# DoorSensor-v1_0.net
KiCad netlist of a schematic drawn in EAGLE
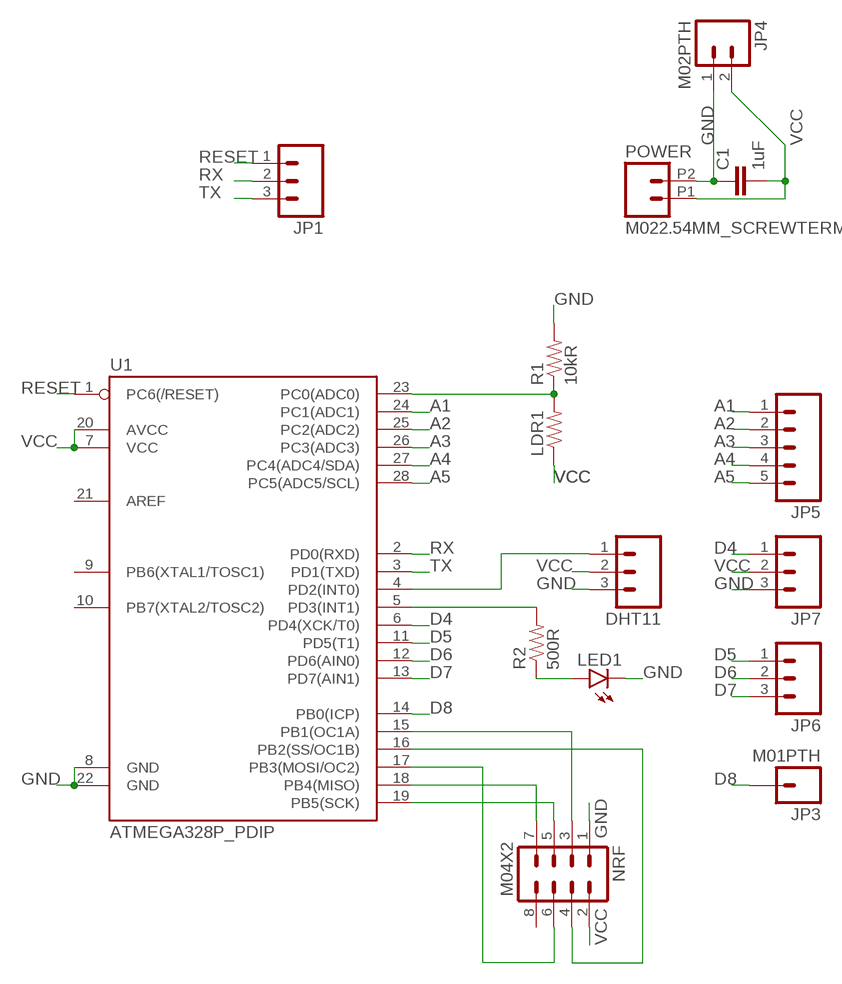
[diagram p0: schematic, sheet 1]

(export (version "E")
  (design (tool "Eeschema 10.0.6"))
  (components
    (comp (ref "C1")
      (value "1uF")
      (footprint "eagle-import:CAP-PTH-SMALL")
      (libsource (lib "eagle-import") (part "CAPPTH"))
    )
    (comp (ref "DHT11")
      (value "M03PTH")
      (footprint "eagle-import:1X03")
      (libsource (lib "eagle-import") (part "M03PTH"))
    )
    (comp (ref "JP1")
      (value "M03PTH")
      (footprint "eagle-import:1X03")
      (libsource (lib "eagle-import") (part "M03PTH"))
    )
    (comp (ref "JP3")
      (value "M01PTH")
      (footprint "eagle-import:1X01")
      (libsource (lib "eagle-import") (part "M01PTH"))
    )
    (comp (ref "JP4")
      (value "M02PTH")
      (footprint "eagle-import:1X02")
      (libsource (lib "eagle-import") (part "M02PTH"))
    )
    (comp (ref "JP5")
      (value "M05PTH")
      (footprint "eagle-import:1X05")
      (libsource (lib "eagle-import") (part "M05PTH"))
    )
    (comp (ref "JP6")
      (value "M03PTH")
      (footprint "eagle-import:1X03")
      (libsource (lib "eagle-import") (part "M03PTH"))
    )
    (comp (ref "JP7")
      (value "M03PTH")
      (footprint "eagle-import:1X03")
      (libsource (lib "eagle-import") (part "M03PTH"))
    )
    (comp (ref "LDR1")
      (value "RESISTORKIT")
      (footprint "eagle-import:AXIAL-0.3-KIT")
      (libsource (lib "eagle-import") (part "RESISTORKIT"))
    )
    (comp (ref "LED1")
      (value "LED3MM")
      (footprint "eagle-import:LED3MM")
      (libsource (lib "eagle-import") (part "LED3MM"))
    )
    (comp (ref "NRF")
      (value "M04X2")
      (footprint "eagle-import:2X4")
      (libsource (lib "eagle-import") (part "M04X2"))
    )
    (comp (ref "POWER")
      (value "M022.54MM_SCREWTERM")
      (footprint "eagle-import:1X02_2.54_SCREWTERM")
      (libsource (lib "eagle-import") (part "M022.54MM_SCREWTERM"))
    )
    (comp (ref "R1")
      (value "10kR")
      (footprint "eagle-import:AXIAL-0.3-KIT")
      (libsource (lib "eagle-import") (part "RESISTORKIT"))
    )
    (comp (ref "R2")
      (value "500R")
      (footprint "eagle-import:AXIAL-0.3-KIT")
      (libsource (lib "eagle-import") (part "RESISTORKIT"))
    )
    (comp (ref "U1")
      (value "ATMEGA328P_PDIP")
      (footprint "eagle-import:DIL28-3")
      (libsource (lib "eagle-import") (part "ATMEGA328P_PDIP"))
    )
  )
  (nets
    (net (code "1") (name "/A1") (class "Default")
      (node (ref "JP5") (pin "1") (pinfunction "1_1") (pintype "passive"))
      (node (ref "U1") (pin "24") (pinfunction "PC1(ADC1)_24") (pintype "bidirectional"))
    )
    (net (code "2") (name "/A2") (class "Default")
      (node (ref "JP5") (pin "2") (pinfunction "2_2") (pintype "passive"))
      (node (ref "U1") (pin "25") (pinfunction "PC2(ADC2)_25") (pintype "bidirectional"))
    )
    (net (code "3") (name "/A3") (class "Default")
      (node (ref "JP5") (pin "3") (pinfunction "3_3") (pintype "passive"))
      (node (ref "U1") (pin "26") (pinfunction "PC3(ADC3)_26") (pintype "bidirectional"))
    )
    (net (code "4") (name "/A4") (class "Default")
      (node (ref "JP5") (pin "4") (pinfunction "4_4") (pintype "passive"))
      (node (ref "U1") (pin "27") (pinfunction "PC4(ADC4/SDA)_27") (pintype "bidirectional"))
    )
    (net (code "5") (name "/A5") (class "Default")
      (node (ref "JP5") (pin "5") (pinfunction "5_5") (pintype "passive"))
      (node (ref "U1") (pin "28") (pinfunction "PC5(ADC5/SCL)_28") (pintype "bidirectional"))
    )
    (net (code "6") (name "/D4") (class "Default")
      (node (ref "JP7") (pin "1") (pinfunction "1_1") (pintype "passive"))
      (node (ref "U1") (pin "6") (pinfunction "PD4(XCK/T0)_6") (pintype "bidirectional"))
    )
    (net (code "7") (name "/D5") (class "Default")
      (node (ref "JP6") (pin "1") (pinfunction "1_1") (pintype "passive"))
      (node (ref "U1") (pin "11") (pinfunction "PD5(T1)_11") (pintype "bidirectional"))
    )
    (net (code "8") (name "/D6") (class "Default")
      (node (ref "JP6") (pin "2") (pinfunction "2_2") (pintype "passive"))
      (node (ref "U1") (pin "12") (pinfunction "PD6(AIN0)_12") (pintype "bidirectional"))
    )
    (net (code "9") (name "/D7") (class "Default")
      (node (ref "JP6") (pin "3") (pinfunction "3_3") (pintype "passive"))
      (node (ref "U1") (pin "13") (pinfunction "PD7(AIN1)_13") (pintype "bidirectional"))
    )
    (net (code "10") (name "/D8") (class "Default")
      (node (ref "JP3") (pin "1") (pinfunction "1_1") (pintype "passive"))
      (node (ref "U1") (pin "14") (pinfunction "PB0(ICP)_14") (pintype "bidirectional"))
    )
    (net (code "11") (name "/GND") (class "Default")
      (node (ref "C1") (pin "1") (pinfunction "1_1") (pintype "passive"))
      (node (ref "DHT11") (pin "3") (pinfunction "3_3") (pintype "passive"))
      (node (ref "JP4") (pin "1") (pinfunction "1_1") (pintype "passive"))
      (node (ref "JP7") (pin "3") (pinfunction "3_3") (pintype "passive"))
      (node (ref "LED1") (pin "K") (pinfunction "C_K") (pintype "passive"))
      (node (ref "NRF") (pin "1") (pinfunction "1_1") (pintype "passive"))
      (node (ref "POWER") (pin "P2") (pinfunction "2_P2") (pintype "passive"))
      (node (ref "R1") (pin "P$2") (pinfunction "2_P$2") (pintype "passive"))
      (node (ref "U1") (pin "22") (pinfunction "GND_22") (pintype "bidirectional"))
      (node (ref "U1") (pin "8") (pinfunction "GND_8") (pintype "bidirectional"))
    )
    (net (code "12") (name "/RESET") (class "Default")
      (node (ref "JP1") (pin "1") (pinfunction "1_1") (pintype "passive"))
      (node (ref "U1") (pin "1") (pinfunction "PC6(/RESET)_1") (pintype "bidirectional"))
    )
    (net (code "13") (name "/RX") (class "Default")
      (node (ref "JP1") (pin "2") (pinfunction "2_2") (pintype "passive"))
      (node (ref "U1") (pin "2") (pinfunction "PD0(RXD)_2") (pintype "bidirectional"))
    )
    (net (code "14") (name "/TX") (class "Default")
      (node (ref "JP1") (pin "3") (pinfunction "3_3") (pintype "passive"))
      (node (ref "U1") (pin "3") (pinfunction "PD1(TXD)_3") (pintype "bidirectional"))
    )
    (net (code "15") (name "/VCC") (class "Default")
      (node (ref "C1") (pin "2") (pinfunction "2_2") (pintype "passive"))
      (node (ref "DHT11") (pin "2") (pinfunction "2_2") (pintype "passive"))
      (node (ref "JP4") (pin "2") (pinfunction "2_2") (pintype "passive"))
      (node (ref "JP7") (pin "2") (pinfunction "2_2") (pintype "passive"))
      (node (ref "LDR1") (pin "P$1") (pinfunction "1_P$1") (pintype "passive"))
      (node (ref "NRF") (pin "2") (pinfunction "2_2") (pintype "passive"))
      (node (ref "POWER") (pin "P1") (pinfunction "1_P1") (pintype "passive"))
      (node (ref "U1") (pin "20") (pinfunction "AVCC_20") (pintype "bidirectional"))
      (node (ref "U1") (pin "7") (pinfunction "VCC_7") (pintype "bidirectional"))
    )
    (net (code "16") (name "Net-(LDR1-2)") (class "Default")
      (node (ref "LDR1") (pin "P$2") (pinfunction "2_P$2") (pintype "passive"))
      (node (ref "R1") (pin "P$1") (pinfunction "1_P$1") (pintype "passive"))
      (node (ref "U1") (pin "23") (pinfunction "PC0(ADC0)_23") (pintype "bidirectional"))
    )
    (net (code "17") (name "Net-(R2-1)") (class "Default")
      (node (ref "LED1") (pin "A") (pinfunction "A_A") (pintype "passive"))
      (node (ref "R2") (pin "P$1") (pinfunction "1_P$1") (pintype "passive"))
    )
    (net (code "18") (name "Net-(R2-2)") (class "Default")
      (node (ref "R2") (pin "P$2") (pinfunction "2_P$2") (pintype "passive"))
      (node (ref "U1") (pin "5") (pinfunction "PD3(INT1)_5") (pintype "bidirectional"))
    )
    (net (code "19") (name "Net-(U1-PB1(OC1A))") (class "Default")
      (node (ref "NRF") (pin "3") (pinfunction "3_3") (pintype "passive"))
      (node (ref "U1") (pin "15") (pinfunction "PB1(OC1A)_15") (pintype "bidirectional"))
    )
    (net (code "20") (name "Net-(U1-PB2(SS{slash}OC1B))") (class "Default")
      (node (ref "NRF") (pin "4") (pinfunction "4_4") (pintype "passive"))
      (node (ref "U1") (pin "16") (pinfunction "PB2(SS/OC1B)_16") (pintype "bidirectional"))
    )
    (net (code "21") (name "Net-(U1-PB3(MOSI{slash}OC2))") (class "Default")
      (node (ref "NRF") (pin "6") (pinfunction "6_6") (pintype "passive"))
      (node (ref "U1") (pin "17") (pinfunction "PB3(MOSI/OC2)_17") (pintype "bidirectional"))
    )
    (net (code "22") (name "Net-(U1-PB4(MISO))") (class "Default")
      (node (ref "NRF") (pin "7") (pinfunction "7_7") (pintype "passive"))
      (node (ref "U1") (pin "18") (pinfunction "PB4(MISO)_18") (pintype "bidirectional"))
    )
    (net (code "23") (name "Net-(U1-PB5(SCK))") (class "Default")
      (node (ref "NRF") (pin "5") (pinfunction "5_5") (pintype "passive"))
      (node (ref "U1") (pin "19") (pinfunction "PB5(SCK)_19") (pintype "bidirectional"))
    )
    (net (code "24") (name "Net-(U1-PD2(INT0))") (class "Default")
      (node (ref "DHT11") (pin "1") (pinfunction "1_1") (pintype "passive"))
      (node (ref "U1") (pin "4") (pinfunction "PD2(INT0)_4") (pintype "bidirectional"))
    )
    (net (code "25") (name "unconnected-(NRF-Pad8)") (class "Default")
      (node (ref "NRF") (pin "8") (pinfunction "8_8") (pintype "passive"))
    )
    (net (code "26") (name "unconnected-(U1-AREF-Pad21)") (class "Default")
      (node (ref "U1") (pin "21") (pinfunction "AREF_21") (pintype "bidirectional"))
    )
    (net (code "27") (name "unconnected-(U1-PB6(XTAL1{slash}TOSC1)-Pad9)") (class "Default")
      (node (ref "U1") (pin "9") (pinfunction "PB6(XTAL1/TOSC1)_9") (pintype "bidirectional"))
    )
    (net (code "28") (name "unconnected-(U1-PB7(XTAL2{slash}TOSC2)-Pad10)") (class "Default")
      (node (ref "U1") (pin "10") (pinfunction "PB7(XTAL2/TOSC2)_10") (pintype "bidirectional"))
    )
  )
)
